# 3V3_LDO.net
KiCad netlist of a schematic drawn in Altium Designer
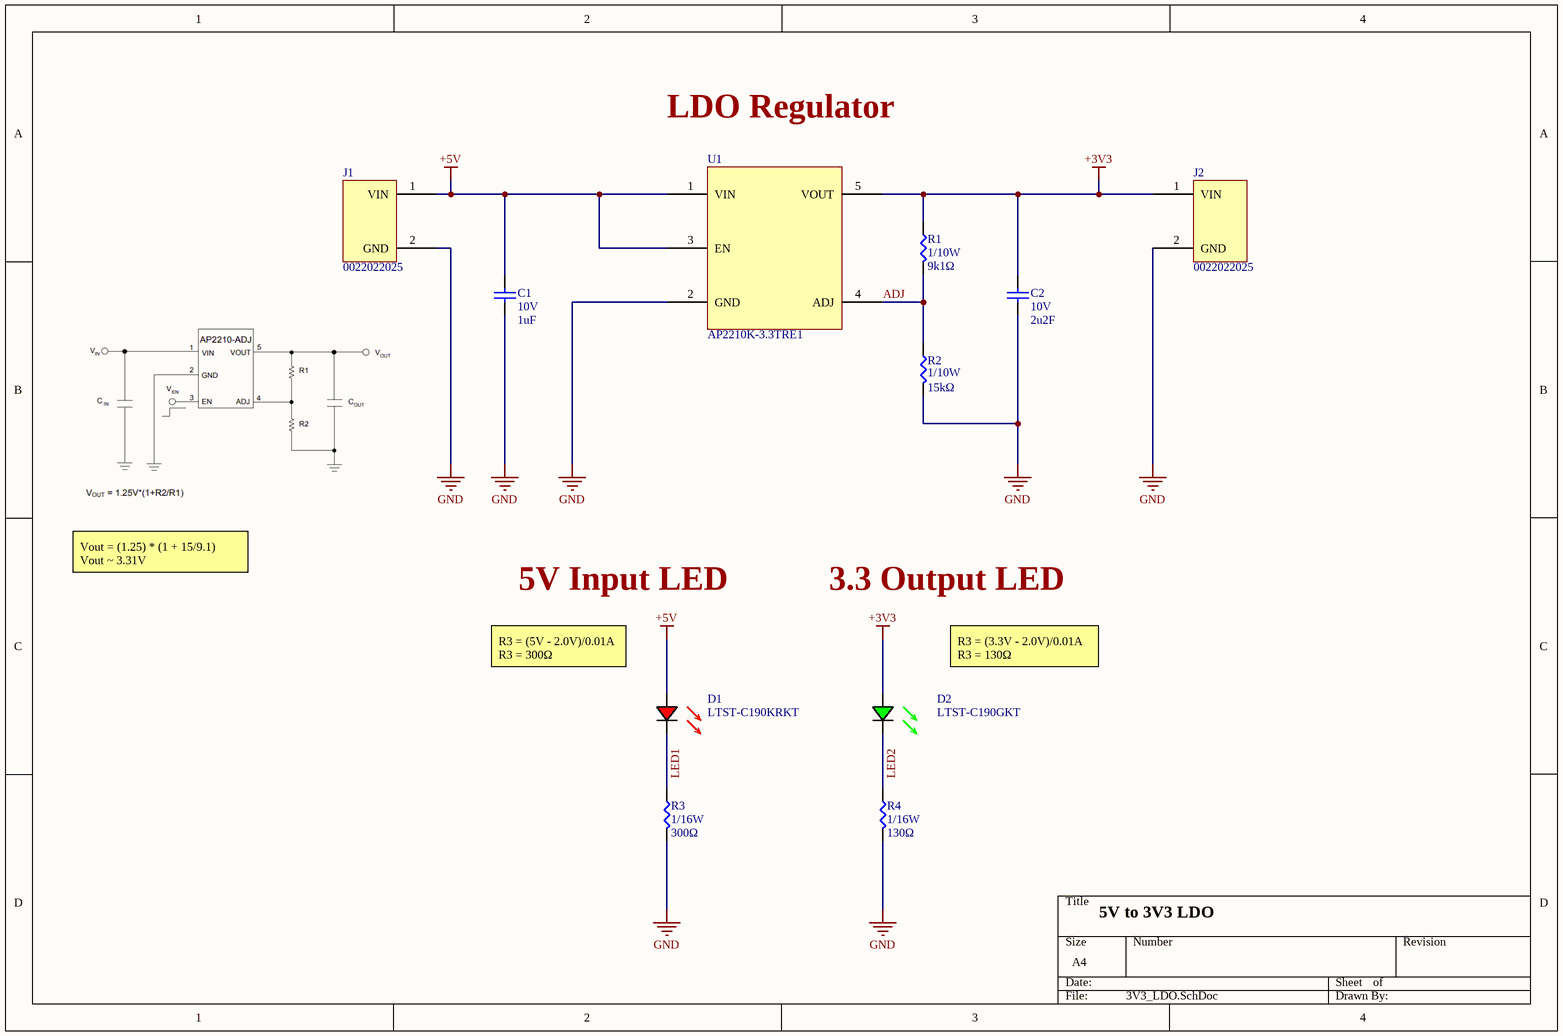
[diagram p0: 3V3_LDO.SchDoc]

(export (version "E")
  (design (tool "Eeschema 10.0.6"))
  (components
    (comp (ref "C1")
      (value "1uF")
      (footprint "CAP0805")
      (description "CAP CER 1UF 10V X5R 0603")
      (fields (field (name "VOLTAGE RATING") "10V") (field (name "Comment") "GRM188R61A105KA61D"))
      (libsource (lib "Bootcamp_Schematic_Library") (part "GRM188R61A105KA61D"))
    )
    (comp (ref "C2")
      (value "2u2F")
      (footprint "CAP0805")
      (description "CAP CER 2.2UF 10V X7R 0603")
      (fields (field (name "VOLTAGE RATING") "10V") (field (name "Comment") "GRM188R71A225KE15D"))
      (libsource (lib "Bootcamp_Schematic_Library") (part "GRM188R71A225KE15D"))
    )
    (comp (ref "D1")
      (value "LTST-C190KRKT")
      (footprint "LED0603")
      (description "LED RED CLEAR CHIP SMD 0603")
      (libsource (lib "Bootcamp_Schematic_Library") (part "LTST-C190KRKT"))
    )
    (comp (ref "D2")
      (value "LTST-C190GKT")
      (footprint "LED0603")
      (description "LED GREEN CLEAR CHIP SMD 0603")
      (libsource (lib "Bootcamp_Schematic_Library") (part "LTST-C190GKT"))
    )
    (comp (ref "J1")
      (value "0022022025")
      (footprint "0022022025")
      (description "2 Position Receptacle Connector 0.100\" (2.54mm) Through Hole Tin")
      (libsource (lib "") (part "0022022025_1"))
    )
    (comp (ref "J2")
      (value "0022022025")
      (footprint "0022022025")
      (description "2 Position Receptacle Connector 0.100\" (2.54mm) Through Hole Tin")
      (libsource (lib "Bootcamp_Schematic_Library") (part "0022022025"))
    )
    (comp (ref "R1")
      (value "9k1Ω")
      (footprint "RES0603")
      (description "RES 9.1K OHM 1% 1/10W 0603")
      (fields (field (name "POWER RATING") "1/10W") (field (name "Comment") "RC0603FR-079K1L"))
      (libsource (lib "Bootcamp_Schematic_Library") (part "RC0603FR-079K1L"))
    )
    (comp (ref "R2")
      (value "15kΩ")
      (footprint "RES0603")
      (description "RES 15K OHM 1% 1/10W 0603")
      (fields
        (field (name "MANUFACTURER") "YAGEO")
        (field (name "RATING") "1/10W")
        (field (name "Comment") "RC0603FR-0715KL")
      )
      (libsource (lib "Bootcamp_Schematic_Library") (part "RC0603FR-0715KL"))
    )
    (comp (ref "R3")
      (value "300Ω")
      (footprint "RES0603")
      (description "RES 300 OHM 5% 1/16W 0402")
      (fields (field (name "POWER RATING") "1/16W") (field (name "Comment") "RC0402JR-07300RL"))
      (libsource (lib "Bootcamp_Schematic_Library") (part "RC0402JR-07300RL"))
    )
    (comp (ref "R4")
      (value "130Ω")
      (footprint "RES0603")
      (description "RES 130 OHM 1% 1/16W 0402")
      (fields (field (name "POWER RATING") "1/16W") (field (name "Comment") "RC0402FR-07130RL"))
      (libsource (lib "Bootcamp_Schematic_Library") (part "RC0402FR-07130RL"))
    )
    (comp (ref "U1")
      (value "AP2210K-3.3TRE1")
      (footprint "AP2210K-3.3TRE1")
      (description "IC REG LINEAR 3.3V 300MA SOT23-5")
      (libsource (lib "Bootcamp_Schematic_Library") (part "AP2210K-3.3TRE1"))
    )
  )
  (nets
    (net (code "1") (name "+3V3") (class "Default")
      (node (ref "C2") (pin "2") (pinfunction "2_2") (pintype "passive"))
      (node (ref "D2") (pin "1") (pintype "passive"))
      (node (ref "J2") (pin "1") (pinfunction "VIN_1") (pintype "passive"))
      (node (ref "R1") (pin "2") (pinfunction "2_2") (pintype "passive"))
      (node (ref "U1") (pin "5") (pinfunction "VOUT_5") (pintype "passive"))
    )
    (net (code "2") (name "+5V") (class "Default")
      (node (ref "C1") (pin "2") (pinfunction "2_2") (pintype "passive"))
      (node (ref "D1") (pin "1") (pintype "passive"))
      (node (ref "J1") (pin "1") (pinfunction "VIN_1") (pintype "passive"))
      (node (ref "U1") (pin "1") (pinfunction "VIN_1") (pintype "passive"))
      (node (ref "U1") (pin "3") (pinfunction "EN_3") (pintype "passive"))
    )
    (net (code "3") (name "/ADJ") (class "Default")
      (node (ref "R1") (pin "1") (pinfunction "1_1") (pintype "passive"))
      (node (ref "R2") (pin "2") (pinfunction "2_2") (pintype "passive"))
      (node (ref "U1") (pin "4") (pinfunction "ADJ_4") (pintype "passive"))
    )
    (net (code "4") (name "/LED1") (class "Default")
      (node (ref "D1") (pin "2") (pintype "passive"))
      (node (ref "R3") (pin "2") (pinfunction "2_2") (pintype "passive"))
    )
    (net (code "5") (name "/LED2") (class "Default")
      (node (ref "D2") (pin "2") (pintype "passive"))
      (node (ref "R4") (pin "2") (pinfunction "2_2") (pintype "passive"))
    )
    (net (code "6") (name "GND") (class "Default")
      (node (ref "C1") (pin "1") (pinfunction "1_1") (pintype "passive"))
      (node (ref "C2") (pin "1") (pinfunction "1_1") (pintype "passive"))
      (node (ref "J1") (pin "2") (pinfunction "GND_2") (pintype "passive"))
      (node (ref "J2") (pin "2") (pinfunction "GND_2") (pintype "passive"))
      (node (ref "R2") (pin "1") (pinfunction "1_1") (pintype "passive"))
      (node (ref "R3") (pin "1") (pinfunction "1_1") (pintype "passive"))
      (node (ref "R4") (pin "1") (pinfunction "1_1") (pintype "passive"))
      (node (ref "U1") (pin "2") (pinfunction "GND_2") (pintype "passive"))
    )
  )
)
